# power.net
KiCad netlist of a schematic drawn in EAGLE
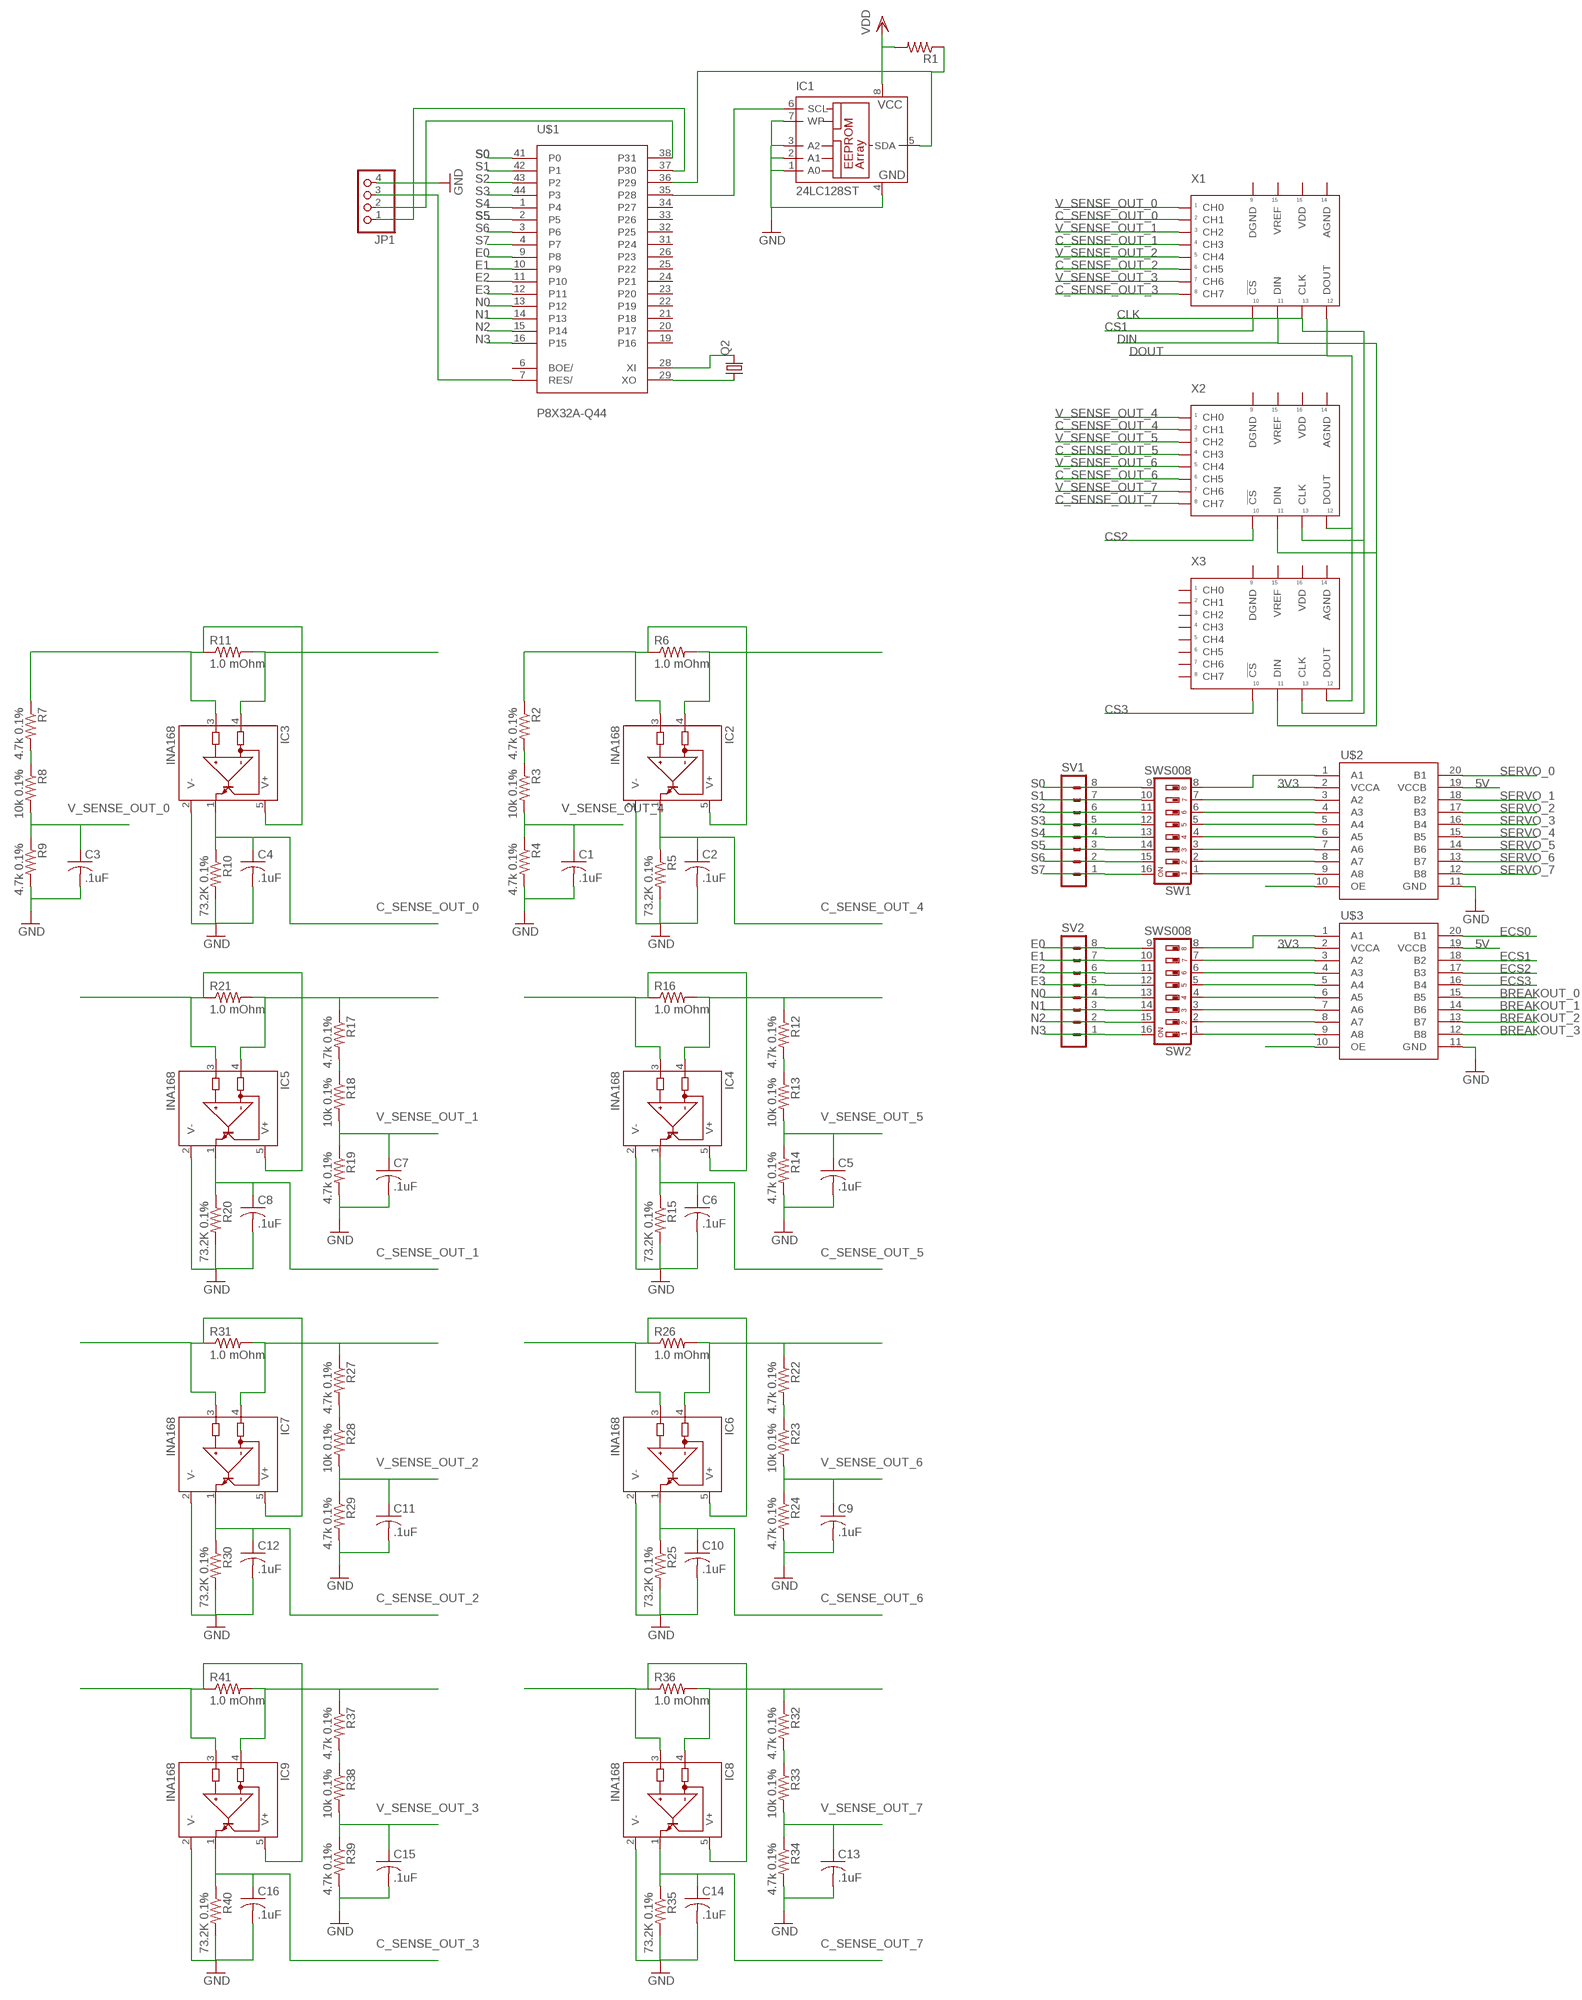
[diagram p0: schematic, sheet 1]

(export (version "E")
  (design (tool "Eeschema 10.0.6"))
  (components
    (comp (ref "C1")
      (value ".1uF")
      (footprint "eagle-import:C0805")
      (libsource (lib "eagle-import") (part "C-USC0805"))
    )
    (comp (ref "C2")
      (value ".1uF")
      (footprint "eagle-import:C0805")
      (libsource (lib "eagle-import") (part "C-USC0805"))
    )
    (comp (ref "C3")
      (value ".1uF")
      (footprint "eagle-import:C0805")
      (libsource (lib "eagle-import") (part "C-USC0805"))
    )
    (comp (ref "C4")
      (value ".1uF")
      (footprint "eagle-import:C0805")
      (libsource (lib "eagle-import") (part "C-USC0805"))
    )
    (comp (ref "C5")
      (value ".1uF")
      (footprint "eagle-import:C0805")
      (libsource (lib "eagle-import") (part "C-USC0805"))
    )
    (comp (ref "C6")
      (value ".1uF")
      (footprint "eagle-import:C0805")
      (libsource (lib "eagle-import") (part "C-USC0805"))
    )
    (comp (ref "C7")
      (value ".1uF")
      (footprint "eagle-import:C0805")
      (libsource (lib "eagle-import") (part "C-USC0805"))
    )
    (comp (ref "C8")
      (value ".1uF")
      (footprint "eagle-import:C0805")
      (libsource (lib "eagle-import") (part "C-USC0805"))
    )
    (comp (ref "C9")
      (value ".1uF")
      (footprint "eagle-import:C0805")
      (libsource (lib "eagle-import") (part "C-USC0805"))
    )
    (comp (ref "C10")
      (value ".1uF")
      (footprint "eagle-import:C0805")
      (libsource (lib "eagle-import") (part "C-USC0805"))
    )
    (comp (ref "C11")
      (value ".1uF")
      (footprint "eagle-import:C0805")
      (libsource (lib "eagle-import") (part "C-USC0805"))
    )
    (comp (ref "C12")
      (value ".1uF")
      (footprint "eagle-import:C0805")
      (libsource (lib "eagle-import") (part "C-USC0805"))
    )
    (comp (ref "C13")
      (value ".1uF")
      (footprint "eagle-import:C0805")
      (libsource (lib "eagle-import") (part "C-USC0805"))
    )
    (comp (ref "C14")
      (value ".1uF")
      (footprint "eagle-import:C0805")
      (libsource (lib "eagle-import") (part "C-USC0805"))
    )
    (comp (ref "C15")
      (value ".1uF")
      (footprint "eagle-import:C0805")
      (libsource (lib "eagle-import") (part "C-USC0805"))
    )
    (comp (ref "C16")
      (value ".1uF")
      (footprint "eagle-import:C0805")
      (libsource (lib "eagle-import") (part "C-USC0805"))
    )
    (comp (ref "IC1")
      (value "24LC128ST")
      (footprint "eagle-import:TSSOP8")
      (fields (field (name "MF") "MICROCHIP") (field (name "MPN") "24LC128-I/ST"))
      (libsource (lib "eagle-import") (part "24STLC128"))
    )
    (comp (ref "IC2")
      (value "INA168")
      (footprint "eagle-import:SOT23-5")
      (fields (field (name "MF") "TEXAS INSTRUMENTS") (field (name "MPN") "INA168NA/250"))
      (libsource (lib "eagle-import") (part "INA168"))
    )
    (comp (ref "IC3")
      (value "INA168")
      (footprint "eagle-import:SOT23-5")
      (fields (field (name "MF") "TEXAS INSTRUMENTS") (field (name "MPN") "INA168NA/250"))
      (libsource (lib "eagle-import") (part "INA168"))
    )
    (comp (ref "IC4")
      (value "INA168")
      (footprint "eagle-import:SOT23-5")
      (fields (field (name "MF") "TEXAS INSTRUMENTS") (field (name "MPN") "INA168NA/250"))
      (libsource (lib "eagle-import") (part "INA168"))
    )
    (comp (ref "IC5")
      (value "INA168")
      (footprint "eagle-import:SOT23-5")
      (fields (field (name "MF") "TEXAS INSTRUMENTS") (field (name "MPN") "INA168NA/250"))
      (libsource (lib "eagle-import") (part "INA168"))
    )
    (comp (ref "IC6")
      (value "INA168")
      (footprint "eagle-import:SOT23-5")
      (fields (field (name "MF") "TEXAS INSTRUMENTS") (field (name "MPN") "INA168NA/250"))
      (libsource (lib "eagle-import") (part "INA168"))
    )
    (comp (ref "IC7")
      (value "INA168")
      (footprint "eagle-import:SOT23-5")
      (fields (field (name "MF") "TEXAS INSTRUMENTS") (field (name "MPN") "INA168NA/250"))
      (libsource (lib "eagle-import") (part "INA168"))
    )
    (comp (ref "IC8")
      (value "INA168")
      (footprint "eagle-import:SOT23-5")
      (fields (field (name "MF") "TEXAS INSTRUMENTS") (field (name "MPN") "INA168NA/250"))
      (libsource (lib "eagle-import") (part "INA168"))
    )
    (comp (ref "IC9")
      (value "INA168")
      (footprint "eagle-import:SOT23-5")
      (fields (field (name "MF") "TEXAS INSTRUMENTS") (field (name "MPN") "INA168NA/250"))
      (libsource (lib "eagle-import") (part "INA168"))
    )
    (comp (ref "JP1")
      (value "PINHD-1X4/90")
      (footprint "eagle-import:1X04_90")
      (libsource (lib "eagle-import") (part "PINHD-1X4/90"))
    )
    (comp (ref "Q2")
      (value "CRYSTALHC49S")
      (footprint "eagle-import:HC49_S")
      (libsource (lib "eagle-import") (part "CRYSTALHC49S"))
    )
    (comp (ref "R1")
      (value "R-US_M0805")
      (footprint "eagle-import:M0805")
      (libsource (lib "eagle-import") (part "resistor_R-US_M0805"))
    )
    (comp (ref "R2")
      (value "4.7k 0.1%")
      (footprint "eagle-import:0805")
      (libsource (lib "eagle-import") (part "RESISTOR0805-RES"))
    )
    (comp (ref "R3")
      (value "10k 0.1%")
      (footprint "eagle-import:0805")
      (libsource (lib "eagle-import") (part "RESISTOR0805-RES"))
    )
    (comp (ref "R4")
      (value "4.7k 0.1%")
      (footprint "eagle-import:0805")
      (libsource (lib "eagle-import") (part "RESISTOR0805-RES"))
    )
    (comp (ref "R5")
      (value "73.2K 0.1%")
      (footprint "eagle-import:0805")
      (libsource (lib "eagle-import") (part "RESISTOR0805-RES"))
    )
    (comp (ref "R6")
      (value "1.0 mOhm")
      (footprint "eagle-import:R2512")
      (libsource (lib "eagle-import") (part "R-US_R2512"))
    )
    (comp (ref "R7")
      (value "4.7k 0.1%")
      (footprint "eagle-import:0805")
      (libsource (lib "eagle-import") (part "RESISTOR0805-RES"))
    )
    (comp (ref "R8")
      (value "10k 0.1%")
      (footprint "eagle-import:0805")
      (libsource (lib "eagle-import") (part "RESISTOR0805-RES"))
    )
    (comp (ref "R9")
      (value "4.7k 0.1%")
      (footprint "eagle-import:0805")
      (libsource (lib "eagle-import") (part "RESISTOR0805-RES"))
    )
    (comp (ref "R10")
      (value "73.2K 0.1%")
      (footprint "eagle-import:0805")
      (libsource (lib "eagle-import") (part "RESISTOR0805-RES"))
    )
    (comp (ref "R11")
      (value "1.0 mOhm")
      (footprint "eagle-import:R2512")
      (libsource (lib "eagle-import") (part "R-US_R2512"))
    )
    (comp (ref "R12")
      (value "4.7k 0.1%")
      (footprint "eagle-import:0805")
      (libsource (lib "eagle-import") (part "RESISTOR0805-RES"))
    )
    (comp (ref "R13")
      (value "10k 0.1%")
      (footprint "eagle-import:0805")
      (libsource (lib "eagle-import") (part "RESISTOR0805-RES"))
    )
    (comp (ref "R14")
      (value "4.7k 0.1%")
      (footprint "eagle-import:0805")
      (libsource (lib "eagle-import") (part "RESISTOR0805-RES"))
    )
    (comp (ref "R15")
      (value "73.2K 0.1%")
      (footprint "eagle-import:0805")
      (libsource (lib "eagle-import") (part "RESISTOR0805-RES"))
    )
    (comp (ref "R16")
      (value "1.0 mOhm")
      (footprint "eagle-import:R2512")
      (libsource (lib "eagle-import") (part "R-US_R2512"))
    )
    (comp (ref "R17")
      (value "4.7k 0.1%")
      (footprint "eagle-import:0805")
      (libsource (lib "eagle-import") (part "RESISTOR0805-RES"))
    )
    (comp (ref "R18")
      (value "10k 0.1%")
      (footprint "eagle-import:0805")
      (libsource (lib "eagle-import") (part "RESISTOR0805-RES"))
    )
    (comp (ref "R19")
      (value "4.7k 0.1%")
      (footprint "eagle-import:0805")
      (libsource (lib "eagle-import") (part "RESISTOR0805-RES"))
    )
    (comp (ref "R20")
      (value "73.2K 0.1%")
      (footprint "eagle-import:0805")
      (libsource (lib "eagle-import") (part "RESISTOR0805-RES"))
    )
    (comp (ref "R21")
      (value "1.0 mOhm")
      (footprint "eagle-import:R2512")
      (libsource (lib "eagle-import") (part "R-US_R2512"))
    )
    (comp (ref "R22")
      (value "4.7k 0.1%")
      (footprint "eagle-import:0805")
      (libsource (lib "eagle-import") (part "RESISTOR0805-RES"))
    )
    (comp (ref "R23")
      (value "10k 0.1%")
      (footprint "eagle-import:0805")
      (libsource (lib "eagle-import") (part "RESISTOR0805-RES"))
    )
    (comp (ref "R24")
      (value "4.7k 0.1%")
      (footprint "eagle-import:0805")
      (libsource (lib "eagle-import") (part "RESISTOR0805-RES"))
    )
    (comp (ref "R25")
      (value "73.2K 0.1%")
      (footprint "eagle-import:0805")
      (libsource (lib "eagle-import") (part "RESISTOR0805-RES"))
    )
    (comp (ref "R26")
      (value "1.0 mOhm")
      (footprint "eagle-import:R2512")
      (libsource (lib "eagle-import") (part "R-US_R2512"))
    )
    (comp (ref "R27")
      (value "4.7k 0.1%")
      (footprint "eagle-import:0805")
      (libsource (lib "eagle-import") (part "RESISTOR0805-RES"))
    )
    (comp (ref "R28")
      (value "10k 0.1%")
      (footprint "eagle-import:0805")
      (libsource (lib "eagle-import") (part "RESISTOR0805-RES"))
    )
    (comp (ref "R29")
      (value "4.7k 0.1%")
      (footprint "eagle-import:0805")
      (libsource (lib "eagle-import") (part "RESISTOR0805-RES"))
    )
    (comp (ref "R30")
      (value "73.2K 0.1%")
      (footprint "eagle-import:0805")
      (libsource (lib "eagle-import") (part "RESISTOR0805-RES"))
    )
    (comp (ref "R31")
      (value "1.0 mOhm")
      (footprint "eagle-import:R2512")
      (libsource (lib "eagle-import") (part "R-US_R2512"))
    )
    (comp (ref "R32")
      (value "4.7k 0.1%")
      (footprint "eagle-import:0805")
      (libsource (lib "eagle-import") (part "RESISTOR0805-RES"))
    )
    (comp (ref "R33")
      (value "10k 0.1%")
      (footprint "eagle-import:0805")
      (libsource (lib "eagle-import") (part "RESISTOR0805-RES"))
    )
    (comp (ref "R34")
      (value "4.7k 0.1%")
      (footprint "eagle-import:0805")
      (libsource (lib "eagle-import") (part "RESISTOR0805-RES"))
    )
    (comp (ref "R35")
      (value "73.2K 0.1%")
      (footprint "eagle-import:0805")
      (libsource (lib "eagle-import") (part "RESISTOR0805-RES"))
    )
    (comp (ref "R36")
      (value "1.0 mOhm")
      (footprint "eagle-import:R2512")
      (libsource (lib "eagle-import") (part "R-US_R2512"))
    )
    (comp (ref "R37")
      (value "4.7k 0.1%")
      (footprint "eagle-import:0805")
      (libsource (lib "eagle-import") (part "RESISTOR0805-RES"))
    )
    (comp (ref "R38")
      (value "10k 0.1%")
      (footprint "eagle-import:0805")
      (libsource (lib "eagle-import") (part "RESISTOR0805-RES"))
    )
    (comp (ref "R39")
      (value "4.7k 0.1%")
      (footprint "eagle-import:0805")
      (libsource (lib "eagle-import") (part "RESISTOR0805-RES"))
    )
    (comp (ref "R40")
      (value "73.2K 0.1%")
      (footprint "eagle-import:0805")
      (libsource (lib "eagle-import") (part "RESISTOR0805-RES"))
    )
    (comp (ref "R41")
      (value "1.0 mOhm")
      (footprint "eagle-import:R2512")
      (libsource (lib "eagle-import") (part "R-US_R2512"))
    )
    (comp (ref "SV1")
      (value "MA08-1")
      (footprint "eagle-import:MA08-1")
      (libsource (lib "eagle-import") (part "MA08-1"))
    )
    (comp (ref "SV2")
      (value "MA08-1")
      (footprint "eagle-import:MA08-1")
      (libsource (lib "eagle-import") (part "MA08-1"))
    )
    (comp (ref "SW1")
      (value "SWS008")
      (footprint "eagle-import:SMS-008")
      (libsource (lib "eagle-import") (part "SWS008"))
    )
    (comp (ref "SW2")
      (value "SWS008")
      (footprint "eagle-import:SMS-008")
      (libsource (lib "eagle-import") (part "SWS008"))
    )
    (comp (ref "U$1")
      (value "P8X32A-Q44")
      (footprint "eagle-import:P8X32A-Q44")
      (libsource (lib "eagle-import") (part "P8X32A-Q44"))
    )
    (comp (ref "U$2")
      (value "TXB0108PWR")
      (footprint "eagle-import:TSSOP20")
      (libsource (lib "eagle-import") (part "TXB0108PWR"))
    )
    (comp (ref "U$3")
      (value "TXB0108PWR")
      (footprint "eagle-import:TSSOP20")
      (libsource (lib "eagle-import") (part "TXB0108PWR"))
    )
    (comp (ref "X1")
      (value "21298ESMD")
      (footprint "eagle-import:PDIP16")
      (libsource (lib "eagle-import") (part "21298ESMD"))
    )
    (comp (ref "X2")
      (value "21298ESMD")
      (footprint "eagle-import:PDIP16")
      (libsource (lib "eagle-import") (part "21298ESMD"))
    )
    (comp (ref "X3")
      (value "21298ESMD")
      (footprint "eagle-import:PDIP16")
      (libsource (lib "eagle-import") (part "21298ESMD"))
    )
  )
  (nets
    (net (code "1") (name "/3V3") (class "Default")
      (node (ref "U$2") (pin "2") (pinfunction "VCCA_2") (pintype "bidirectional"))
      (node (ref "U$3") (pin "2") (pinfunction "VCCA_2") (pintype "bidirectional"))
    )
    (net (code "2") (name "/5V") (class "Default")
      (node (ref "U$2") (pin "19") (pinfunction "VCCB_19") (pintype "bidirectional"))
      (node (ref "U$3") (pin "19") (pinfunction "VCCB_19") (pintype "bidirectional"))
    )
    (net (code "3") (name "/BREAKOUT_0") (class "Default")
      (node (ref "U$3") (pin "15") (pinfunction "B5_15") (pintype "bidirectional"))
    )
    (net (code "4") (name "/BREAKOUT_1") (class "Default")
      (node (ref "U$3") (pin "14") (pinfunction "B6_14") (pintype "bidirectional"))
    )
    (net (code "5") (name "/BREAKOUT_2") (class "Default")
      (node (ref "U$3") (pin "13") (pinfunction "B7_13") (pintype "bidirectional"))
    )
    (net (code "6") (name "/BREAKOUT_3") (class "Default")
      (node (ref "U$3") (pin "12") (pinfunction "B8_12") (pintype "bidirectional"))
    )
    (net (code "7") (name "/CLK") (class "Default")
      (node (ref "X1") (pin "P$13") (pinfunction "CLK_P$13") (pintype "bidirectional"))
      (node (ref "X2") (pin "P$13") (pinfunction "CLK_P$13") (pintype "bidirectional"))
      (node (ref "X3") (pin "P$13") (pinfunction "CLK_P$13") (pintype "bidirectional"))
    )
    (net (code "8") (name "/CS1") (class "Default")
      (node (ref "X1") (pin "P$10") (pinfunction "~{CS}_P$10") (pintype "bidirectional"))
    )
    (net (code "9") (name "/CS2") (class "Default")
      (node (ref "X2") (pin "P$10") (pinfunction "~{CS}_P$10") (pintype "bidirectional"))
    )
    (net (code "10") (name "/CS3") (class "Default")
      (node (ref "X3") (pin "P$10") (pinfunction "~{CS}_P$10") (pintype "bidirectional"))
    )
    (net (code "11") (name "/C_SENSE_OUT_0") (class "Default")
      (node (ref "C4") (pin "1") (pinfunction "1_1") (pintype "passive"))
      (node (ref "IC3") (pin "1") (pinfunction "OUT_1") (pintype "output"))
      (node (ref "R10") (pin "1") (pinfunction "1_1") (pintype "passive"))
      (node (ref "X1") (pin "P$2") (pinfunction "CH1_P$2") (pintype "bidirectional"))
    )
    (net (code "12") (name "/C_SENSE_OUT_1") (class "Default")
      (node (ref "C8") (pin "1") (pinfunction "1_1") (pintype "passive"))
      (node (ref "IC5") (pin "1") (pinfunction "OUT_1") (pintype "output"))
      (node (ref "R20") (pin "1") (pinfunction "1_1") (pintype "passive"))
      (node (ref "X1") (pin "P$4") (pinfunction "CH3_P$4") (pintype "bidirectional"))
    )
    (net (code "13") (name "/C_SENSE_OUT_2") (class "Default")
      (node (ref "C12") (pin "1") (pinfunction "1_1") (pintype "passive"))
      (node (ref "IC7") (pin "1") (pinfunction "OUT_1") (pintype "output"))
      (node (ref "R30") (pin "1") (pinfunction "1_1") (pintype "passive"))
      (node (ref "X1") (pin "P$6") (pinfunction "CH5_P$6") (pintype "bidirectional"))
    )
    (net (code "14") (name "/C_SENSE_OUT_3") (class "Default")
      (node (ref "C16") (pin "1") (pinfunction "1_1") (pintype "passive"))
      (node (ref "IC9") (pin "1") (pinfunction "OUT_1") (pintype "output"))
      (node (ref "R40") (pin "1") (pinfunction "1_1") (pintype "passive"))
      (node (ref "X1") (pin "P$8") (pinfunction "CH7_P$8") (pintype "bidirectional"))
    )
    (net (code "15") (name "/C_SENSE_OUT_4") (class "Default")
      (node (ref "C2") (pin "1") (pinfunction "1_1") (pintype "passive"))
      (node (ref "IC2") (pin "1") (pinfunction "OUT_1") (pintype "output"))
      (node (ref "R5") (pin "1") (pinfunction "1_1") (pintype "passive"))
      (node (ref "X2") (pin "P$2") (pinfunction "CH1_P$2") (pintype "bidirectional"))
    )
    (net (code "16") (name "/C_SENSE_OUT_5") (class "Default")
      (node (ref "C6") (pin "1") (pinfunction "1_1") (pintype "passive"))
      (node (ref "IC4") (pin "1") (pinfunction "OUT_1") (pintype "output"))
      (node (ref "R15") (pin "1") (pinfunction "1_1") (pintype "passive"))
      (node (ref "X2") (pin "P$4") (pinfunction "CH3_P$4") (pintype "bidirectional"))
    )
    (net (code "17") (name "/C_SENSE_OUT_6") (class "Default")
      (node (ref "C10") (pin "1") (pinfunction "1_1") (pintype "passive"))
      (node (ref "IC6") (pin "1") (pinfunction "OUT_1") (pintype "output"))
      (node (ref "R25") (pin "1") (pinfunction "1_1") (pintype "passive"))
      (node (ref "X2") (pin "P$6") (pinfunction "CH5_P$6") (pintype "bidirectional"))
    )
    (net (code "18") (name "/C_SENSE_OUT_7") (class "Default")
      (node (ref "C14") (pin "1") (pinfunction "1_1") (pintype "passive"))
      (node (ref "IC8") (pin "1") (pinfunction "OUT_1") (pintype "output"))
      (node (ref "R35") (pin "1") (pinfunction "1_1") (pintype "passive"))
      (node (ref "X2") (pin "P$8") (pinfunction "CH7_P$8") (pintype "bidirectional"))
    )
    (net (code "19") (name "/DIN") (class "Default")
      (node (ref "X1") (pin "P$11") (pinfunction "DIN_P$11") (pintype "bidirectional"))
      (node (ref "X2") (pin "P$11") (pinfunction "DIN_P$11") (pintype "bidirectional"))
      (node (ref "X3") (pin "P$11") (pinfunction "DIN_P$11") (pintype "bidirectional"))
    )
    (net (code "20") (name "/DOUT") (class "Default")
      (node (ref "X1") (pin "P$12") (pinfunction "DOUT_P$12") (pintype "bidirectional"))
      (node (ref "X2") (pin "P$12") (pinfunction "DOUT_P$12") (pintype "bidirectional"))
      (node (ref "X3") (pin "P$12") (pinfunction "DOUT_P$12") (pintype "bidirectional"))
    )
    (net (code "21") (name "/E0") (class "Default")
      (node (ref "SV2") (pin "8") (pinfunction "8_8") (pintype "passive"))
      (node (ref "SW2") (pin "9") (pinfunction "9_9") (pintype "passive"))
      (node (ref "U$1") (pin "9") (pinfunction "P8_9") (pintype "bidirectional"))
    )
    (net (code "22") (name "/E1") (class "Default")
      (node (ref "SV2") (pin "7") (pinfunction "7_7") (pintype "passive"))
      (node (ref "SW2") (pin "10") (pinfunction "10_10") (pintype "passive"))
      (node (ref "U$1") (pin "10") (pinfunction "P9_10") (pintype "bidirectional"))
    )
    (net (code "23") (name "/E2") (class "Default")
      (node (ref "SV2") (pin "6") (pinfunction "6_6") (pintype "passive"))
      (node (ref "SW2") (pin "11") (pinfunction "11_11") (pintype "passive"))
      (node (ref "U$1") (pin "11") (pinfunction "P10_11") (pintype "bidirectional"))
    )
    (net (code "24") (name "/E3") (class "Default")
      (node (ref "SV2") (pin "5") (pinfunction "5_5") (pintype "passive"))
      (node (ref "SW2") (pin "12") (pinfunction "12_12") (pintype "passive"))
      (node (ref "U$1") (pin "12") (pinfunction "P11_12") (pintype "bidirectional"))
    )
    (net (code "25") (name "/ECS0") (class "Default")
      (node (ref "U$3") (pin "20") (pinfunction "B1_20") (pintype "bidirectional"))
    )
    (net (code "26") (name "/ECS1") (class "Default")
      (node (ref "U$3") (pin "18") (pinfunction "B2_18") (pintype "bidirectional"))
    )
    (net (code "27") (name "/ECS2") (class "Default")
      (node (ref "U$3") (pin "17") (pinfunction "B3_17") (pintype "bidirectional"))
    )
    (net (code "28") (name "/ECS3") (class "Default")
      (node (ref "U$3") (pin "16") (pinfunction "B4_16") (pintype "bidirectional"))
    )
    (net (code "29") (name "/N0") (class "Default")
      (node (ref "SV2") (pin "4") (pinfunction "4_4") (pintype "passive"))
      (node (ref "SW2") (pin "13") (pinfunction "13_13") (pintype "passive"))
      (node (ref "U$1") (pin "13") (pinfunction "P12_13") (pintype "bidirectional"))
    )
    (net (code "30") (name "/N1") (class "Default")
      (node (ref "SV2") (pin "3") (pinfunction "3_3") (pintype "passive"))
      (node (ref "SW2") (pin "14") (pinfunction "14_14") (pintype "passive"))
      (node (ref "U$1") (pin "14") (pinfunction "P13_14") (pintype "bidirectional"))
    )
    (net (code "31") (name "/N2") (class "Default")
      (node (ref "SV2") (pin "2") (pinfunction "2_2") (pintype "passive"))
      (node (ref "SW2") (pin "15") (pinfunction "15_15") (pintype "passive"))
      (node (ref "U$1") (pin "15") (pinfunction "P14_15") (pintype "bidirectional"))
    )
    (net (code "32") (name "/N3") (class "Default")
      (node (ref "SV2") (pin "1") (pinfunction "1_1") (pintype "passive"))
      (node (ref "SW2") (pin "16") (pinfunction "16_16") (pintype "passive"))
      (node (ref "U$1") (pin "16") (pinfunction "P15_16") (pintype "bidirectional"))
    )
    (net (code "33") (name "/S0") (class "Default")
      (node (ref "SV1") (pin "8") (pinfunction "8_8") (pintype "passive"))
      (node (ref "SW1") (pin "9") (pinfunction "9_9") (pintype "passive"))
      (node (ref "U$1") (pin "41") (pinfunction "P0_41") (pintype "bidirectional"))
    )
    (net (code "34") (name "/S1") (class "Default")
      (node (ref "SV1") (pin "7") (pinfunction "7_7") (pintype "passive"))
      (node (ref "SW1") (pin "10") (pinfunction "10_10") (pintype "passive"))
      (node (ref "U$1") (pin "42") (pinfunction "P1_42") (pintype "bidirectional"))
    )
    (net (code "35") (name "/S2") (class "Default")
      (node (ref "SV1") (pin "6") (pinfunction "6_6") (pintype "passive"))
      (node (ref "SW1") (pin "11") (pinfunction "11_11") (pintype "passive"))
      (node (ref "U$1") (pin "43") (pinfunction "P2_43") (pintype "bidirectional"))
    )
    (net (code "36") (name "/S3") (class "Default")
      (node (ref "SV1") (pin "5") (pinfunction "5_5") (pintype "passive"))
      (node (ref "SW1") (pin "12") (pinfunction "12_12") (pintype "passive"))
      (node (ref "U$1") (pin "44") (pinfunction "P3_44") (pintype "bidirectional"))
    )
    (net (code "37") (name "/S4") (class "Default")
      (node (ref "SV1") (pin "4") (pinfunction "4_4") (pintype "passive"))
      (node (ref "SW1") (pin "13") (pinfunction "13_13") (pintype "passive"))
      (node (ref "U$1") (pin "1") (pinfunction "P4_1") (pintype "bidirectional"))
    )
    (net (code "38") (name "/S5") (class "Default")
      (node (ref "SV1") (pin "3") (pinfunction "3_3") (pintype "passive"))
      (node (ref "SW1") (pin "14") (pinfunction "14_14") (pintype "passive"))
      (node (ref "U$1") (pin "2") (pinfunction "P5_2") (pintype "bidirectional"))
    )
    (net (code "39") (name "/S6") (class "Default")
      (node (ref "SV1") (pin "2") (pinfunction "2_2") (pintype "passive"))
      (node (ref "SW1") (pin "15") (pinfunction "15_15") (pintype "passive"))
      (node (ref "U$1") (pin "3") (pinfunction "P6_3") (pintype "bidirectional"))
    )
    (net (code "40") (name "/S7") (class "Default")
      (node (ref "SV1") (pin "1") (pinfunction "1_1") (pintype "passive"))
      (node (ref "SW1") (pin "16") (pinfunction "16_16") (pintype "passive"))
      (node (ref "U$1") (pin "4") (pinfunction "P7_4") (pintype "bidirectional"))
    )
    (net (code "41") (name "/SERVO_0") (class "Default")
      (node (ref "U$2") (pin "20") (pinfunction "B1_20") (pintype "bidirectional"))
    )
    (net (code "42") (name "/SERVO_1") (class "Default")
      (node (ref "U$2") (pin "18") (pinfunction "B2_18") (pintype "bidirectional"))
    )
    (net (code "43") (name "/SERVO_2") (class "Default")
      (node (ref "U$2") (pin "17") (pinfunction "B3_17") (pintype "bidirectional"))
    )
    (net (code "44") (name "/SERVO_3") (class "Default")
      (node (ref "U$2") (pin "16") (pinfunction "B4_16") (pintype "bidirectional"))
    )
    (net (code "45") (name "/SERVO_4") (class "Default")
      (node (ref "U$2") (pin "15") (pinfunction "B5_15") (pintype "bidirectional"))
    )
    (net (code "46") (name "/SERVO_5") (class "Default")
      (node (ref "U$2") (pin "14") (pinfunction "B6_14") (pintype "bidirectional"))
    )
    (net (code "47") (name "/SERVO_6") (class "Default")
      (node (ref "U$2") (pin "13") (pinfunction "B7_13") (pintype "bidirectional"))
    )
    (net (code "48") (name "/SERVO_7") (class "Default")
      (node (ref "U$2") (pin "12") (pinfunction "B8_12") (pintype "bidirectional"))
    )
    (net (code "49") (name "/V_SENSE_OUT_0") (class "Default")
      (node (ref "C3") (pin "1") (pinfunction "1_1") (pintype "passive"))
      (node (ref "R8") (pin "2") (pinfunction "2_2") (pintype "passive"))
      (node (ref "R9") (pin "1") (pinfunction "1_1") (pintype "passive"))
      (node (ref "X1") (pin "P$1") (pinfunction "CH0_P$1") (pintype "bidirectional"))
    )
    (net (code "50") (name "/V_SENSE_OUT_1") (class "Default")
      (node (ref "C7") (pin "1") (pinfunction "1_1") (pintype "passive"))
      (node (ref "R18") (pin "2") (pinfunction "2_2") (pintype "passive"))
      (node (ref "R19") (pin "1") (pinfunction "1_1") (pintype "passive"))
      (node (ref "X1") (pin "P$3") (pinfunction "CH2_P$3") (pintype "bidirectional"))
    )
    (net (code "51") (name "/V_SENSE_OUT_2") (class "Default")
      (node (ref "C11") (pin "1") (pinfunction "1_1") (pintype "passive"))
      (node (ref "R28") (pin "2") (pinfunction "2_2") (pintype "passive"))
      (node (ref "R29") (pin "1") (pinfunction "1_1") (pintype "passive"))
      (node (ref "X1") (pin "P$5") (pinfunction "CH4_P$5") (pintype "bidirectional"))
    )
    (net (code "52") (name "/V_SENSE_OUT_3") (class "Default")
      (node (ref "C15") (pin "1") (pinfunction "1_1") (pintype "passive"))
      (node (ref "R38") (pin "2") (pinfunction "2_2") (pintype "passive"))
      (node (ref "R39") (pin "1") (pinfunction "1_1") (pintype "passive"))
      (node (ref "X1") (pin "P$7") (pinfunction "CH6_P$7") (pintype "bidirectional"))
    )
    (net (code "53") (name "/V_SENSE_OUT_4") (class "Default")
      (node (ref "C1") (pin "1") (pinfunction "1_1") (pintype "passive"))
      (node (ref "R3") (pin "2") (pinfunction "2_2") (pintype "passive"))
      (node (ref "R4") (pin "1") (pinfunction "1_1") (pintype "passive"))
      (node (ref "X2") (pin "P$1") (pinfunction "CH0_P$1") (pintype "bidirectional"))
    )
    (net (code "54") (name "/V_SENSE_OUT_5") (class "Default")
      (node (ref "C5") (pin "1") (pinfunction "1_1") (pintype "passive"))
      (node (ref "R13") (pin "2") (pinfunction "2_2") (pintype "passive"))
      (node (ref "R14") (pin "1") (pinfunction "1_1") (pintype "passive"))
      (node (ref "X2") (pin "P$3") (pinfunction "CH2_P$3") (pintype "bidirectional"))
    )
    (net (code "55") (name "/V_SENSE_OUT_6") (class "Default")
      (node (ref "C9") (pin "1") (pinfunction "1_1") (pintype "passive"))
      (node (ref "R23") (pin "2") (pinfunction "2_2") (pintype "passive"))
      (node (ref "R24") (pin "1") (pinfunction "1_1") (pintype "passive"))
      (node (ref "X2") (pin "P$5") (pinfunction "CH4_P$5") (pintype "bidirectional"))
    )
    (net (code "56") (name "/V_SENSE_OUT_7") (class "Default")
      (node (ref "C13") (pin "1") (pinfunction "1_1") (pintype "passive"))
      (node (ref "R33") (pin "2") (pinfunction "2_2") (pintype "passive"))
      (node (ref "R34") (pin "1") (pinfunction "1_1") (pintype "passive"))
      (node (ref "X2") (pin "P$7") (pinfunction "CH6_P$7") (pintype "bidirectional"))
    )
    (net (code "57") (name "GND") (class "Default")
      (node (ref "C1") (pin "2") (pinfunction "2_2") (pintype "passive"))
      (node (ref "C10") (pin "2") (pinfunction "2_2") (pintype "passive"))
      (node (ref "C11") (pin "2") (pinfunction "2_2") (pintype "passive"))
      (node (ref "C12") (pin "2") (pinfunction "2_2") (pintype "passive"))
      (node (ref "C13") (pin "2") (pinfunction "2_2") (pintype "passive"))
      (node (ref "C14") (pin "2") (pinfunction "2_2") (pintype "passive"))
      (node (ref "C15") (pin "2") (pinfunction "2_2") (pintype "passive"))
      (node (ref "C16") (pin "2") (pinfunction "2_2") (pintype "passive"))
      (node (ref "C2") (pin "2") (pinfunction "2_2") (pintype "passive"))
      (node (ref "C3") (pin "2") (pinfunction "2_2") (pintype "passive"))
      (node (ref "C4") (pin "2") (pinfunction "2_2") (pintype "passive"))
      (node (ref "C5") (pin "2") (pinfunction "2_2") (pintype "passive"))
      (node (ref "C6") (pin "2") (pinfunction "2_2") (pintype "passive"))
      (node (ref "C7") (pin "2") (pinfunction "2_2") (pintype "passive"))
      (node (ref "C8") (pin "2") (pinfunction "2_2") (pintype "passive"))
      (node (ref "C9") (pin "2") (pinfunction "2_2") (pintype "passive"))
      (node (ref "IC1") (pin "1") (pinfunction "A0_1") (pintype "input"))
      (node (ref "IC1") (pin "2") (pinfunction "A1_2") (pintype "input"))
      (node (ref "IC1") (pin "3") (pinfunction "A2_3") (pintype "input"))
      (node (ref "IC1") (pin "4") (pinfunction "GND_4") (pintype "power_in"))
      (node (ref "IC1") (pin "7") (pinfunction "WP_7") (pintype "input"))
      (node (ref "IC2") (pin "2") (pinfunction "V-_2") (pintype "power_in"))
      (node (ref "IC3") (pin "2") (pinfunction "V-_2") (pintype "power_in"))
      (node (ref "IC4") (pin "2") (pinfunction "V-_2") (pintype "power_in"))
      (node (ref "IC5") (pin "2") (pinfunction "V-_2") (pintype "power_in"))
      (node (ref "IC6") (pin "2") (pinfunction "V-_2") (pintype "power_in"))
      (node (ref "IC7") (pin "2") (pinfunction "V-_2") (pintype "power_in"))
      (node (ref "IC8") (pin "2") (pinfunction "V-_2") (pintype "power_in"))
      (node (ref "IC9") (pin "2") (pinfunction "V-_2") (pintype "power_in"))
      (node (ref "JP1") (pin "4") (pinfunction "4_4") (pintype "passive"))
      (node (ref "R10") (pin "2") (pinfunction "2_2") (pintype "passive"))
      (node (ref "R14") (pin "2") (pinfunction "2_2") (pintype "passive"))
      (node (ref "R15") (pin "2") (pinfunction "2_2") (pintype "passive"))
      (node (ref "R19") (pin "2") (pinfunction "2_2") (pintype "passive"))
      (node (ref "R20") (pin "2") (pinfunction "2_2") (pintype "passive"))
      (node (ref "R24") (pin "2") (pinfunction "2_2") (pintype "passive"))
      (node (ref "R25") (pin "2") (pinfunction "2_2") (pintype "passive"))
      (node (ref "R29") (pin "2") (pinfunction "2_2") (pintype "passive"))
      (node (ref "R30") (pin "2") (pinfunction "2_2") (pintype "passive"))
      (node (ref "R34") (pin "2") (pinfunction "2_2") (pintype "passive"))
      (node (ref "R35") (pin "2") (pinfunction "2_2") (pintype "passive"))
      (node (ref "R39") (pin "2") (pinfunction "2_2") (pintype "passive"))
      (node (ref "R4") (pin "2") (pinfunction "2_2") (pintype "passive"))
      (node (ref "R40") (pin "2") (pinfunction "2_2") (pintype "passive"))
      (node (ref "R5") (pin "2") (pinfunction "2_2") (pintype "passive"))
      (node (ref "R9") (pin "2") (pinfunction "2_2") (pintype "passive"))
      (node (ref "U$2") (pin "11") (pinfunction "GND_11") (pintype "bidirectional"))
      (node (ref "U$3") (pin "11") (pinfunction "GND_11") (pintype "bidirectional"))
    )
    (net (code "58") (name "Net-(IC1-SCL)") (class "Default")
      (node (ref "IC1") (pin "6") (pinfunction "SCL_6") (pintype "input"))
      (node (ref "U$1") (pin "35") (pinfunction "P28_35") (pintype "bidirectional"))
    )
    (net (code "59") (name "Net-(IC1-SDA)") (class "Default")
      (node (ref "IC1") (pin "5") (pinfunction "SDA_5") (pintype "bidirectional"))
      (node (ref "R1") (pin "1") (pinfunction "1_1") (pintype "passive"))
      (node (ref "U$1") (pin "36") (pinfunction "P29_36") (pintype "bidirectional"))
    )
    (net (code "60") (name "Net-(IC2-IN+)") (class "Default")
      (node (ref "IC2") (pin "3") (pinfunction "IN+_3") (pintype "input"))
      (node (ref "IC2") (pin "5") (pinfunction "V+_5") (pintype "power_in"))
      (node (ref "R2") (pin "1") (pinfunction "1_1") (pintype "passive"))
      (node (ref "R6") (pin "1") (pinfunction "1_1") (pintype "passive"))
    )
    (net (code "61") (name "Net-(IC2-IN-)") (class "Default")
      (node (ref "IC2") (pin "4") (pinfunction "IN-_4") (pintype "input"))
      (node (ref "R6") (pin "2") (pinfunction "2_2") (pintype "passive"))
    )
    (net (code "62") (name "Net-(IC3-IN+)") (class "Default")
      (node (ref "IC3") (pin "3") (pinfunction "IN+_3") (pintype "input"))
      (node (ref "IC3") (pin "5") (pinfunction "V+_5") (pintype "power_in"))
      (node (ref "R11") (pin "1") (pinfunction "1_1") (pintype "passive"))
      (node (ref "R7") (pin "1") (pinfunction "1_1") (pintype "passive"))
    )
    (net (code "63") (name "Net-(IC3-IN-)") (class "Default")
      (node (ref "IC3") (pin "4") (pinfunction "IN-_4") (pintype "input"))
      (node (ref "R11") (pin "2") (pinfunction "2_2") (pintype "passive"))
    )
    (net (code "64") (name "Net-(IC4-IN+)") (class "Default")
      (node (ref "IC4") (pin "3") (pinfunction "IN+_3") (pintype "input"))
      (node (ref "IC4") (pin "5") (pinfunction "V+_5") (pintype "power_in"))
      (node (ref "R16") (pin "1") (pinfunction "1_1") (pintype "passive"))
    )
    (net (code "65") (name "Net-(IC4-IN-)") (class "Default")
      (node (ref "IC4") (pin "4") (pinfunction "IN-_4") (pintype "input"))
      (node (ref "R12") (pin "1") (pinfunction "1_1") (pintype "passive"))
      (node (ref "R16") (pin "2") (pinfunction "2_2") (pintype "passive"))
    )
    (net (code "66") (name "Net-(IC5-IN+)") (class "Default")
      (node (ref "IC5") (pin "3") (pinfunction "IN+_3") (pintype "input"))
      (node (ref "IC5") (pin "5") (pinfunction "V+_5") (pintype "power_in"))
      (node (ref "R21") (pin "1") (pinfunction "1_1") (pintype "passive"))
    )
    (net (code "67") (name "Net-(IC5-IN-)") (class "Default")
      (node (ref "IC5") (pin "4") (pinfunction "IN-_4") (pintype "input"))
      (node (ref "R17") (pin "1") (pinfunction "1_1") (pintype "passive"))
      (node (ref "R21") (pin "2") (pinfunction "2_2") (pintype "passive"))
    )
    (net (code "68") (name "Net-(IC6-IN+)") (class "Default")
      (node (ref "IC6") (pin "3") (pinfunction "IN+_3") (pintype "input"))
      (node (ref "IC6") (pin "5") (pinfunction "V+_5") (pintype "power_in"))
      (node (ref "R26") (pin "1") (pinfunction "1_1") (pintype "passive"))
    )
    (net (code "69") (name "Net-(IC6-IN-)") (class "Default")
      (node (ref "IC6") (pin "4") (pinfunction "IN-_4") (pintype "input"))
      (node (ref "R22") (pin "1") (pinfunction "1_1") (pintype "passive"))
      (node (ref "R26") (pin "2") (pinfunction "2_2") (pintype "passive"))
    )
    (net (code "70") (name "Net-(IC7-IN+)") (class "Default")
      (node (ref "IC7") (pin "3") (pinfunction "IN+_3") (pintype "input"))
      (node (ref "IC7") (pin "5") (pinfunction "V+_5") (pintype "power_in"))
      (node (ref "R31") (pin "1") (pinfunction "1_1") (pintype "passive"))
    )
    (net (code "71") (name "Net-(IC7-IN-)") (class "Default")
      (node (ref "IC7") (pin "4") (pinfunction "IN-_4") (pintype "input"))
      (node (ref "R27") (pin "1") (pinfunction "1_1") (pintype "passive"))
      (node (ref "R31") (pin "2") (pinfunction "2_2") (pintype "passive"))
    )
    (net (code "72") (name "Net-(IC8-IN+)") (class "Default")
      (node (ref "IC8") (pin "3") (pinfunction "IN+_3") (pintype "input"))
      (node (ref "IC8") (pin "5") (pinfunction "V+_5") (pintype "power_in"))
      (node (ref "R36") (pin "1") (pinfunction "1_1") (pintype "passive"))
    )
    (net (code "73") (name "Net-(IC8-IN-)") (class "Default")
      (node (ref "IC8") (pin "4") (pinfunction "IN-_4") (pintype "input"))
      (node (ref "R32") (pin "1") (pinfunction "1_1") (pintype "passive"))
      (node (ref "R36") (pin "2") (pinfunction "2_2") (pintype "passive"))
    )
    (net (code "74") (name "Net-(IC9-IN+)") (class "Default")
      (node (ref "IC9") (pin "3") (pinfunction "IN+_3") (pintype "input"))
      (node (ref "IC9") (pin "5") (pinfunction "V+_5") (pintype "power_in"))
      (node (ref "R41") (pin "1") (pinfunction "1_1") (pintype "passive"))
    )
    (net (code "75") (name "Net-(IC9-IN-)") (class "Default")
      (node (ref "IC9") (pin "4") (pinfunction "IN-_4") (pintype "input"))
      (node (ref "R37") (pin "1") (pinfunction "1_1") (pintype "passive"))
      (node (ref "R41") (pin "2") (pinfunction "2_2") (pintype "passive"))
    )
    (net (code "76") (name "Net-(R2-Pad2)") (class "Default")
      (node (ref "R2") (pin "2") (pinfunction "2_2") (pintype "passive"))
      (node (ref "R3") (pin "1") (pinfunction "1_1") (pintype "passive"))
    )
    (net (code "77") (name "Net-(R7-Pad2)") (class "Default")
      (node (ref "R7") (pin "2") (pinfunction "2_2") (pintype "passive"))
      (node (ref "R8") (pin "1") (pinfunction "1_1") (pintype "passive"))
    )
    (net (code "78") (name "Net-(R12-Pad2)") (class "Default")
      (node (ref "R12") (pin "2") (pinfunction "2_2") (pintype "passive"))
      (node (ref "R13") (pin "1") (pinfunction "1_1") (pintype "passive"))
    )
    (net (code "79") (name "Net-(R17-Pad2)") (class "Default")
      (node (ref "R17") (pin "2") (pinfunction "2_2") (pintype "passive"))
      (node (ref "R18") (pin "1") (pinfunction "1_1") (pintype "passive"))
    )
    (net (code "80") (name "Net-(R22-Pad2)") (class "Default")
      (node (ref "R22") (pin "2") (pinfunction "2_2") (pintype "passive"))
      (node (ref "R23") (pin "1") (pinfunction "1_1") (pintype "passive"))
    )
    (net (code "81") (name "Net-(R27-Pad2)") (class "Default")
      (node (ref "R27") (pin "2") (pinfunction "2_2") (pintype "passive"))
      (node (ref "R28") (pin "1") (pinfunction "1_1") (pintype "passive"))
    )
    (net (code "82") (name "Net-(R32-Pad2)") (class "Default")
      (node (ref "R32") (pin "2") (pinfunction "2_2") (pintype "passive"))
      (node (ref "R33") (pin "1") (pinfunction "1_1") (pintype "passive"))
    )
    (net (code "83") (name "Net-(R37-Pad2)") (class "Default")
      (node (ref "R37") (pin "2") (pinfunction "2_2") (pintype "passive"))
      (node (ref "R38") (pin "1") (pinfunction "1_1") (pintype "passive"))
    )
    (net (code "84") (name "Net-(U$1B-P30)") (class "Default")
      (node (ref "JP1") (pin "1") (pinfunction "1_1") (pintype "passive"))
      (node (ref "U$1") (pin "37") (pinfunction "P30_37") (pintype "bidirectional"))
    )
    (net (code "85") (name "Net-(U$1B-P31)") (class "Default")
      (node (ref "JP1") (pin "2") (pinfunction "2_2") (pintype "passive"))
      (node (ref "U$1") (pin "38") (pinfunction "P31_38") (pintype "bidirectional"))
    )
    (net (code "86") (name "Net-(U$1B-RES{slash})") (class "Default")
      (node (ref "JP1") (pin "3") (pinfunction "3_3") (pintype "passive"))
      (node (ref "U$1") (pin "7") (pinfunction "RES/_7") (pintype "bidirectional"))
    )
    (net (code "87") (name "Net-(U$1B-XI)") (class "Default")
      (node (ref "Q2") (pin "2") (pinfunction "2_2") (pintype "passive"))
      (node (ref "U$1") (pin "28") (pinfunction "XI_28") (pintype "input"))
    )
    (net (code "88") (name "Net-(U$1B-XO)") (class "Default")
      (node (ref "Q2") (pin "1") (pinfunction "1_1") (pintype "passive"))
      (node (ref "U$1") (pin "29") (pinfunction "XO_29") (pintype "output"))
    )
    (net (code "89") (name "Net-(U$2-A1)") (class "Default")
      (node (ref "SW1") (pin "8") (pinfunction "8_8") (pintype "passive"))
      (node (ref "U$2") (pin "1") (pinfunction "A1_1") (pintype "bidirectional"))
    )
    (net (code "90") (name "Net-(U$2-A2)") (class "Default")
      (node (ref "SW1") (pin "7") (pinfunction "7_7") (pintype "passive"))
      (node (ref "U$2") (pin "3") (pinfunction "A2_3") (pintype "bidirectional"))
    )
    (net (code "91") (name "Net-(U$2-A3)") (class "Default")
      (node (ref "SW1") (pin "6") (pinfunction "6_6") (pintype "passive"))
      (node (ref "U$2") (pin "4") (pinfunction "A3_4") (pintype "bidirectional"))
    )
    (net (code "92") (name "Net-(U$2-A4)") (class "Default")
      (node (ref "SW1") (pin "5") (pinfunction "5_5") (pintype "passive"))
      (node (ref "U$2") (pin "5") (pinfunction "A4_5") (pintype "bidirectional"))
    )
    (net (code "93") (name "Net-(U$2-A5)") (class "Default")
      (node (ref "SW1") (pin "4") (pinfunction "4_4") (pintype "passive"))
      (node (ref "U$2") (pin "6") (pinfunction "A5_6") (pintype "bidirectional"))
    )
    (net (code "94") (name "Net-(U$2-A6)") (class "Default")
      (node (ref "SW1") (pin "3") (pinfunction "3_3") (pintype "passive"))
      (node (ref "U$2") (pin "7") (pinfunction "A6_7") (pintype "bidirectional"))
    )
    (net (code "95") (name "Net-(U$2-A7)") (class "Default")
      (node (ref "SW1") (pin "2") (pinfunction "2_2") (pintype "passive"))
      (node (ref "U$2") (pin "8") (pinfunction "A7_8") (pintype "bidirectional"))
    )
    (net (code "96") (name "Net-(U$2-A8)") (class "Default")
      (node (ref "SW1") (pin "1") (pinfunction "1_1") (pintype "passive"))
      (node (ref "U$2") (pin "9") (pinfunction "A8_9") (pintype "bidirectional"))
    )
    (net (code "97") (name "Net-(U$3-A1)") (class "Default")
      (node (ref "SW2") (pin "8") (pinfunction "8_8") (pintype "passive"))
      (node (ref "U$3") (pin "1") (pinfunction "A1_1") (pintype "bidirectional"))
    )
    (net (code "98") (name "Net-(U$3-A2)") (class "Default")
      (node (ref "SW2") (pin "7") (pinfunction "7_7") (pintype "passive"))
      (node (ref "U$3") (pin "3") (pinfunction "A2_3") (pintype "bidirectional"))
    )
    (net (code "99") (name "Net-(U$3-A3)") (class "Default")
      (node (ref "SW2") (pin "6") (pinfunction "6_6") (pintype "passive"))
      (node (ref "U$3") (pin "4") (pinfunction "A3_4") (pintype "bidirectional"))
    )
    (net (code "100") (name "Net-(U$3-A4)") (class "Default")
      (node (ref "SW2") (pin "5") (pinfunction "5_5") (pintype "passive"))
      (node (ref "U$3") (pin "5") (pinfunction "A4_5") (pintype "bidirectional"))
    )
    (net (code "101") (name "Net-(U$3-A5)") (class "Default")
      (node (ref "SW2") (pin "4") (pinfunction "4_4") (pintype "passive"))
      (node (ref "U$3") (pin "6") (pinfunction "A5_6") (pintype "bidirectional"))
    )
    (net (code "102") (name "Net-(U$3-A6)") (class "Default")
      (node (ref "SW2") (pin "3") (pinfunction "3_3") (pintype "passive"))
      (node (ref "U$3") (pin "7") (pinfunction "A6_7") (pintype "bidirectional"))
    )
    (net (code "103") (name "Net-(U$3-A7)") (class "Default")
      (node (ref "SW2") (pin "2") (pinfunction "2_2") (pintype "passive"))
      (node (ref "U$3") (pin "8") (pinfunction "A7_8") (pintype "bidirectional"))
    )
    (net (code "104") (name "Net-(U$3-A8)") (class "Default")
      (node (ref "SW2") (pin "1") (pinfunction "1_1") (pintype "passive"))
      (node (ref "U$3") (pin "9") (pinfunction "A8_9") (pintype "bidirectional"))
    )
    (net (code "105") (name "VDD") (class "Default")
      (node (ref "IC1") (pin "8") (pinfunction "VCC_8") (pintype "power_in"))
      (node (ref "R1") (pin "2") (pinfunction "2_2") (pintype "passive"))
    )
    (net (code "106") (name "unconnected-(U$1B-BOE{slash}-Pad6)") (class "Default")
      (node (ref "U$1") (pin "6") (pinfunction "BOE/_6") (pintype "input"))
    )
    (net (code "107") (name "unconnected-(U$1B-P16-Pad19)") (class "Default")
      (node (ref "U$1") (pin "19") (pinfunction "P16_19") (pintype "bidirectional"))
    )
    (net (code "108") (name "unconnected-(U$1B-P17-Pad20)") (class "Default")
      (node (ref "U$1") (pin "20") (pinfunction "P17_20") (pintype "bidirectional"))
    )
    (net (code "109") (name "unconnected-(U$1B-P18-Pad21)") (class "Default")
      (node (ref "U$1") (pin "21") (pinfunction "P18_21") (pintype "bidirectional"))
    )
    (net (code "110") (name "unconnected-(U$1B-P19-Pad22)") (class "Default")
      (node (ref "U$1") (pin "22") (pinfunction "P19_22") (pintype "bidirectional"))
    )
    (net (code "111") (name "unconnected-(U$1B-P20-Pad23)") (class "Default")
      (node (ref "U$1") (pin "23") (pinfunction "P20_23") (pintype "bidirectional"))
    )
    (net (code "112") (name "unconnected-(U$1B-P21-Pad24)") (class "Default")
      (node (ref "U$1") (pin "24") (pinfunction "P21_24") (pintype "bidirectional"))
    )
    (net (code "113") (name "unconnected-(U$1B-P22-Pad25)") (class "Default")
      (node (ref "U$1") (pin "25") (pinfunction "P22_25") (pintype "bidirectional"))
    )
    (net (code "114") (name "unconnected-(U$1B-P23-Pad26)") (class "Default")
      (node (ref "U$1") (pin "26") (pinfunction "P23_26") (pintype "bidirectional"))
    )
    (net (code "115") (name "unconnected-(U$1B-P24-Pad31)") (class "Default")
      (node (ref "U$1") (pin "31") (pinfunction "P24_31") (pintype "bidirectional"))
    )
    (net (code "116") (name "unconnected-(U$1B-P25-Pad32)") (class "Default")
      (node (ref "U$1") (pin "32") (pinfunction "P25_32") (pintype "bidirectional"))
    )
    (net (code "117") (name "unconnected-(U$1B-P26-Pad33)") (class "Default")
      (node (ref "U$1") (pin "33") (pinfunction "P26_33") (pintype "bidirectional"))
    )
    (net (code "118") (name "unconnected-(U$1B-P27-Pad34)") (class "Default")
      (node (ref "U$1") (pin "34") (pinfunction "P27_34") (pintype "bidirectional"))
    )
    (net (code "119") (name "unconnected-(U$2-OE-Pad10)") (class "Default")
      (node (ref "U$2") (pin "10") (pinfunction "OE_10") (pintype "bidirectional"))
    )
    (net (code "120") (name "unconnected-(U$3-OE-Pad10)") (class "Default")
      (node (ref "U$3") (pin "10") (pinfunction "OE_10") (pintype "bidirectional"))
    )
    (net (code "121") (name "unconnected-(X1-AGND-PadP$14)") (class "Default")
      (node (ref "X1") (pin "P$14") (pinfunction "AGND_P$14") (pintype "bidirectional"))
    )
    (net (code "122") (name "unconnected-(X1-DGND-PadP$9)") (class "Default")
      (node (ref "X1") (pin "P$9") (pinfunction "DGND_P$9") (pintype "bidirectional"))
    )
    (net (code "123") (name "unconnected-(X1-VDD-PadP$16)") (class "Default")
      (node (ref "X1") (pin "P$16") (pinfunction "VDD_P$16") (pintype "bidirectional"))
    )
    (net (code "124") (name "unconnected-(X1-VREF-PadP$15)") (class "Default")
      (node (ref "X1") (pin "P$15") (pinfunction "VREF_P$15") (pintype "bidirectional"))
    )
    (net (code "125") (name "unconnected-(X2-AGND-PadP$14)") (class "Default")
      (node (ref "X2") (pin "P$14") (pinfunction "AGND_P$14") (pintype "bidirectional"))
    )
    (net (code "126") (name "unconnected-(X2-DGND-PadP$9)") (class "Default")
      (node (ref "X2") (pin "P$9") (pinfunction "DGND_P$9") (pintype "bidirectional"))
    )
    (net (code "127") (name "unconnected-(X2-VDD-PadP$16)") (class "Default")
      (node (ref "X2") (pin "P$16") (pinfunction "VDD_P$16") (pintype "bidirectional"))
    )
    (net (code "128") (name "unconnected-(X2-VREF-PadP$15)") (class "Default")
      (node (ref "X2") (pin "P$15") (pinfunction "VREF_P$15") (pintype "bidirectional"))
    )
    (net (code "129") (name "unconnected-(X3-AGND-PadP$14)") (class "Default")
      (node (ref "X3") (pin "P$14") (pinfunction "AGND_P$14") (pintype "bidirectional"))
    )
    (net (code "130") (name "unconnected-(X3-CH0-PadP$1)") (class "Default")
      (node (ref "X3") (pin "P$1") (pinfunction "CH0_P$1") (pintype "bidirectional"))
    )
    (net (code "131") (name "unconnected-(X3-CH1-PadP$2)") (class "Default")
      (node (ref "X3") (pin "P$2") (pinfunction "CH1_P$2") (pintype "bidirectional"))
    )
    (net (code "132") (name "unconnected-(X3-CH2-PadP$3)") (class "Default")
      (node (ref "X3") (pin "P$3") (pinfunction "CH2_P$3") (pintype "bidirectional"))
    )
    (net (code "133") (name "unconnected-(X3-CH3-PadP$4)") (class "Default")
      (node (ref "X3") (pin "P$4") (pinfunction "CH3_P$4") (pintype "bidirectional"))
    )
    (net (code "134") (name "unconnected-(X3-CH4-PadP$5)") (class "Default")
      (node (ref "X3") (pin "P$5") (pinfunction "CH4_P$5") (pintype "bidirectional"))
    )
    (net (code "135") (name "unconnected-(X3-CH5-PadP$6)") (class "Default")
      (node (ref "X3") (pin "P$6") (pinfunction "CH5_P$6") (pintype "bidirectional"))
    )
    (net (code "136") (name "unconnected-(X3-CH6-PadP$7)") (class "Default")
      (node (ref "X3") (pin "P$7") (pinfunction "CH6_P$7") (pintype "bidirectional"))
    )
    (net (code "137") (name "unconnected-(X3-CH7-PadP$8)") (class "Default")
      (node (ref "X3") (pin "P$8") (pinfunction "CH7_P$8") (pintype "bidirectional"))
    )
    (net (code "138") (name "unconnected-(X3-DGND-PadP$9)") (class "Default")
      (node (ref "X3") (pin "P$9") (pinfunction "DGND_P$9") (pintype "bidirectional"))
    )
    (net (code "139") (name "unconnected-(X3-VDD-PadP$16)") (class "Default")
      (node (ref "X3") (pin "P$16") (pinfunction "VDD_P$16") (pintype "bidirectional"))
    )
    (net (code "140") (name "unconnected-(X3-VREF-PadP$15)") (class "Default")
      (node (ref "X3") (pin "P$15") (pinfunction "VREF_P$15") (pintype "bidirectional"))
    )
  )
)
